# 21-LAN.net
KiCad netlist of a schematic drawn in Altium Designer
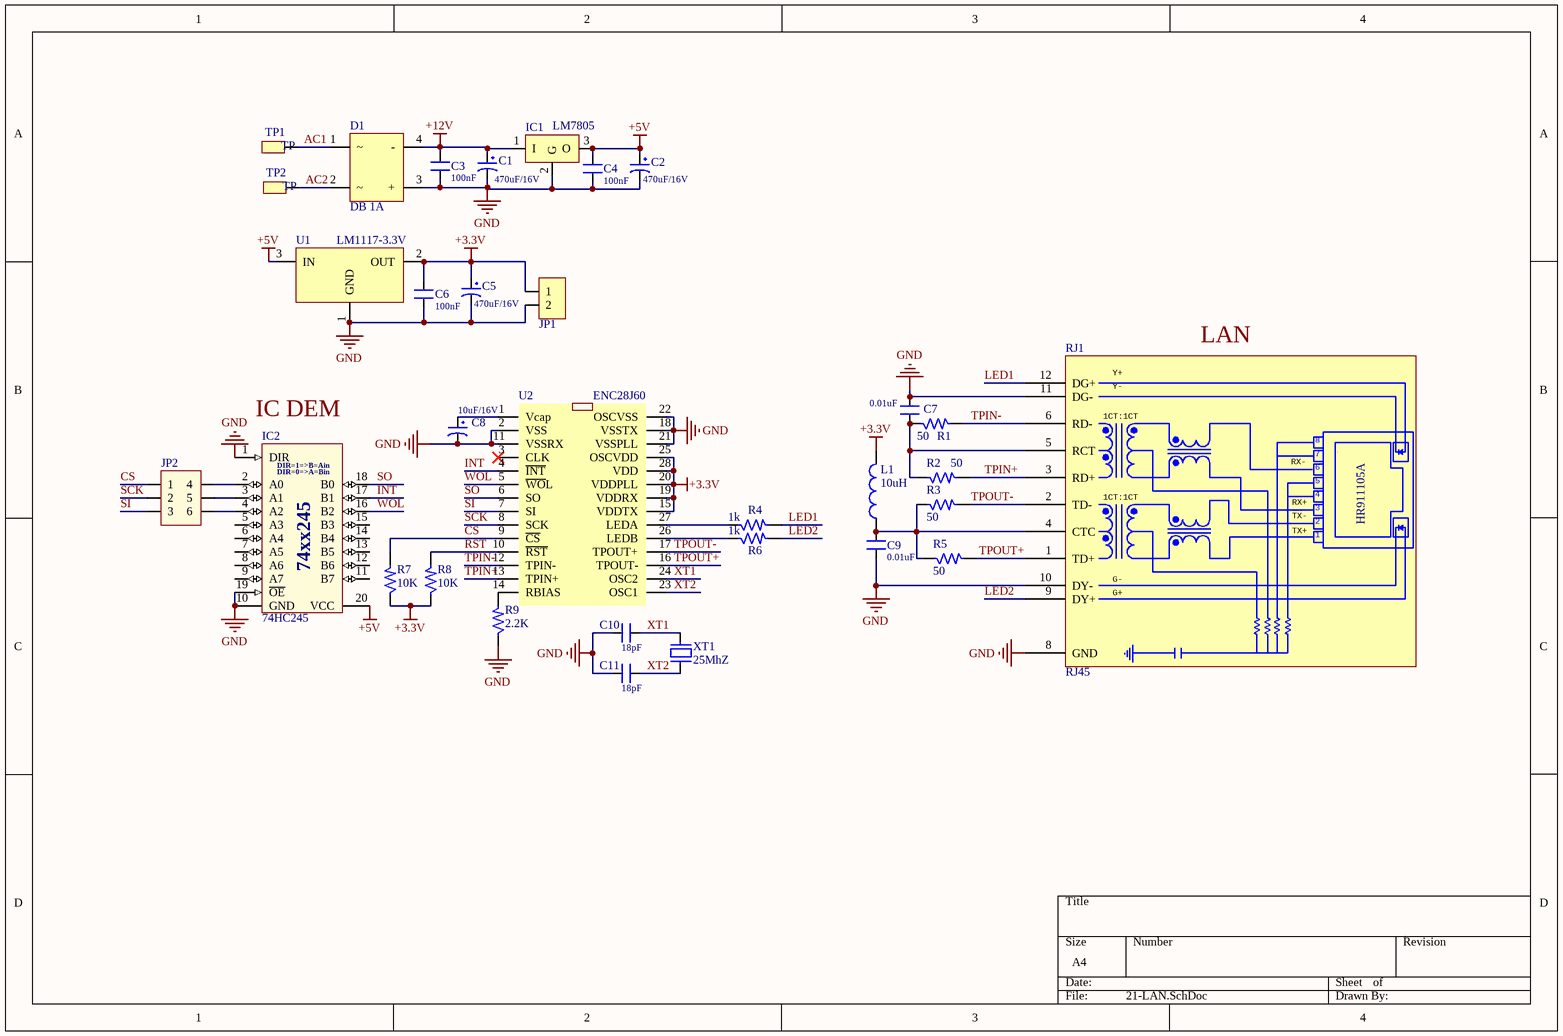
[diagram p0: 21-LAN.SchDoc]

(export (version "E")
  (design (tool "Eeschema 10.0.6"))
  (components
    (comp (ref "C1")
      (value "470uF/16V")
      (footprint "C-TANT-7343")
      (libsource (lib "MrQuan") (part "Capacitor"))
    )
    (comp (ref "C2")
      (value "470uF/16V")
      (footprint "C-TANT-7343")
      (libsource (lib "MrQuan") (part "Capacitor"))
    )
    (comp (ref "C3") (value "100nF") (footprint "CER-0805") (libsource (lib "MrQuan") (part "Ceramic")))
    (comp (ref "C4") (value "100nF") (footprint "CER-0805") (libsource (lib "MrQuan") (part "Ceramic")))
    (comp (ref "C5")
      (value "470uF/16V")
      (footprint "C-TANT-7343")
      (libsource (lib "MrQuan") (part "Capacitor"))
    )
    (comp (ref "C6") (value "100nF") (footprint "CER-0805") (libsource (lib "MrQuan") (part "Ceramic")))
    (comp (ref "C7") (value "0.01uF") (footprint "CER-0805") (libsource (lib "MrQuan") (part "Ceramic")))
    (comp (ref "C8")
      (value "10uF/16V")
      (footprint "C-TANT-7343")
      (libsource (lib "MrQuan") (part "Capacitor"))
    )
    (comp (ref "C9") (value "0.01uF") (footprint "CER-0805") (libsource (lib "MrQuan") (part "Ceramic")))
    (comp (ref "C10") (value "18pF") (footprint "CER-0805") (libsource (lib "MrQuan") (part "Ceramic")))
    (comp (ref "C11") (value "18pF") (footprint "CER-0805") (libsource (lib "MrQuan") (part "Ceramic")))
    (comp (ref "D1")
      (value "DB 1A")
      (footprint "D-DB-1A-SMD")
      (libsource (lib "doAnTotNghiep2017Lib") (part "DB"))
    )
    (comp (ref "IC1")
      (value "LM7805")
      (footprint "TO252-123")
      (description "Positive Voltage Regulator")
      (fields (field (name "PUBLISHER") "Altium Limited"))
      (libsource (lib "LIBRARY") (part "LM78xx"))
    )
    (comp (ref "IC2")
      (value "74HC245")
      (footprint "SO-20B")
      (description "Octal bus tranceiver; 3-state")
      (fields (field (name "COPYRIGHT BY") "VanDungEvn@gmail.com"))
      (libsource (lib "PART") (part "74245"))
    )
    (comp (ref "JP1")
      (value "JP2")
      (footprint "JP2-C1T")
      (description "WR-PHD 2.54 mm Angled Socket Header")
      (fields
        (field (name "MANUFACTURER") "Würth Elektronik eiSos GmbH")
        (field (name "PARTNO") "613002143121")
        (field (name "CREATED BY") "Karrer Zheng")
      )
      (libsource (lib "LIBRARY") (part "JP2"))
    )
    (comp (ref "JP2")
      (value "Connector 3x2")
      (footprint "JP3x2")
      (libsource (lib "syhaunguyen") (part "JP3x2"))
    )
    (comp (ref "L1")
      (value "10uH")
      (footprint "CER-0805")
      (description "Inductor")
      (fields (field (name "PUBLISHER") "Altium Limited"))
      (libsource (lib "VNSKILLS2014-ASM") (part "Inductor"))
    )
    (comp (ref "R1") (value "50") (footprint "RES-0805") (libsource (lib "MrQuan") (part "Res1/4W")))
    (comp (ref "R2") (value "50") (footprint "RES-0805") (libsource (lib "MrQuan") (part "Res1/4W")))
    (comp (ref "R3") (value "50") (footprint "RES-0805") (libsource (lib "MrQuan") (part "Res1/4W")))
    (comp (ref "R4") (value "1k") (footprint "RES-0805") (libsource (lib "MrQuan") (part "Res1/4W")))
    (comp (ref "R5") (value "50") (footprint "RES-0805") (libsource (lib "MrQuan") (part "Res1/4W")))
    (comp (ref "R6") (value "1k") (footprint "RES-0805") (libsource (lib "MrQuan") (part "Res1/4W")))
    (comp (ref "R7") (value "10K") (footprint "RES-0805") (libsource (lib "MrQuan") (part "Res1/4W")))
    (comp (ref "R8") (value "10K") (footprint "RES-0805") (libsource (lib "MrQuan") (part "Res1/4W")))
    (comp (ref "R9") (value "2.2K") (footprint "RES-0805") (libsource (lib "MrQuan") (part "Res1/4W")))
    (comp (ref "RJ1")
      (value "RJ45")
      (footprint "RJ45 Tranfomer")
      (libsource (lib "syhaunguyen") (part "RJ45 - Tranfomer"))
    )
    (comp (ref "TP1")
      (value "1")
      (footprint "TP")
      (description "CONNECT 1")
      (libsource (lib "PART") (part "TP"))
    )
    (comp (ref "TP2")
      (value "1")
      (footprint "TP")
      (description "CONNECT 1")
      (libsource (lib "PART") (part "TP"))
    )
    (comp (ref "U1")
      (value "LM1117-3.3V")
      (footprint "SOT223")
      (description "800mA Low-Dropout Linear Regulator")
      (fields (field (name "CREATOR") "Nguyen Ba Bien"))
      (libsource (lib "LIBRARY") (part "LM1117"))
    )
    (comp (ref "U2") (value "ENC28J60") (footprint "SOP 28N") (libsource (lib "MrQuan") (part "ENC28J60")))
    (comp (ref "XT1") (value "25MhZ") (footprint "XT SMD5032") (libsource (lib "MrQuan") (part "XT")))
  )
  (nets
    (net (code "1") (name "+3.3V") (class "Default")
      (node (ref "C5") (pin "1") (pinfunction "1_1") (pintype "passive"))
      (node (ref "C6") (pin "2") (pinfunction "2_2") (pintype "passive"))
      (node (ref "JP1") (pin "1") (pinfunction "1_1") (pintype "passive"))
      (node (ref "L1") (pin "2") (pinfunction "2_2") (pintype "passive"))
      (node (ref "R7") (pin "1") (pinfunction "1_1") (pintype "passive"))
      (node (ref "R8") (pin "1") (pinfunction "1_1") (pintype "passive"))
      (node (ref "U1") (pin "2") (pinfunction "OUT_2") (pintype "passive"))
      (node (ref "U2") (pin "15") (pinfunction "VDDTX_15") (pintype "passive"))
      (node (ref "U2") (pin "19") (pinfunction "VDDRX_19") (pintype "passive"))
      (node (ref "U2") (pin "20") (pinfunction "VDDPLL_20") (pintype "passive"))
      (node (ref "U2") (pin "25") (pinfunction "OSCVDD_25") (pintype "passive"))
      (node (ref "U2") (pin "28") (pinfunction "VDD_28") (pintype "passive"))
    )
    (net (code "2") (name "+5V") (class "Default")
      (node (ref "C2") (pin "1") (pinfunction "1_1") (pintype "passive"))
      (node (ref "C4") (pin "2") (pinfunction "2_2") (pintype "passive"))
      (node (ref "IC1") (pin "3") (pinfunction "O_3") (pintype "power_in"))
      (node (ref "IC2") (pin "20") (pinfunction "VCC_20") (pintype "power_in"))
      (node (ref "U1") (pin "3") (pinfunction "IN_3") (pintype "passive"))
    )
    (net (code "3") (name "+12V") (class "Default")
      (node (ref "C1") (pin "1") (pinfunction "1_1") (pintype "passive"))
      (node (ref "C3") (pin "2") (pinfunction "2_2") (pintype "passive"))
      (node (ref "D1") (pin "4") (pinfunction "-_4") (pintype "passive"))
      (node (ref "IC1") (pin "1") (pinfunction "I_1") (pintype "power_in"))
    )
    (net (code "4") (name "/AC1") (class "Default")
      (node (ref "D1") (pin "1") (pinfunction "~_1") (pintype "passive"))
      (node (ref "TP1") (pin "TP1") (pinfunction "0_TP1") (pintype "passive"))
    )
    (net (code "5") (name "/AC2") (class "Default")
      (node (ref "D1") (pin "2") (pinfunction "~_2") (pintype "passive"))
      (node (ref "TP2") (pin "TP1") (pinfunction "0_TP1") (pintype "passive"))
    )
    (net (code "6") (name "/CS") (class "Default")
      (node (ref "JP2") (pin "1") (pinfunction "1_1") (pintype "passive"))
      (node (ref "R7") (pin "2") (pinfunction "2_2") (pintype "passive"))
      (node (ref "U2") (pin "9") (pinfunction "~{CS}_9") (pintype "passive"))
    )
    (net (code "8") (name "/INT") (class "Default")
      (node (ref "IC2") (pin "17") (pinfunction "B1_17") (pintype "bidirectional"))
      (node (ref "U2") (pin "4") (pinfunction "~{INT}_4") (pintype "passive"))
    )
    (net (code "10") (name "/LED1") (class "Default")
      (node (ref "R4") (pin "2") (pinfunction "2_2") (pintype "passive"))
      (node (ref "RJ1") (pin "12") (pinfunction "DG+_12") (pintype "passive"))
    )
    (net (code "11") (name "/LED2") (class "Default")
      (node (ref "R6") (pin "2") (pinfunction "2_2") (pintype "passive"))
      (node (ref "RJ1") (pin "9") (pinfunction "DY+_9") (pintype "passive"))
    )
    (net (code "12") (name "/RST") (class "Default")
      (node (ref "R8") (pin "2") (pinfunction "2_2") (pintype "passive"))
      (node (ref "U2") (pin "10") (pinfunction "~{RST}_10") (pintype "passive"))
    )
    (net (code "13") (name "/SCK") (class "Default")
      (node (ref "JP2") (pin "2") (pinfunction "2_2") (pintype "passive"))
      (node (ref "U2") (pin "8") (pinfunction "SCK_8") (pintype "passive"))
    )
    (net (code "14") (name "/SI") (class "Default")
      (node (ref "JP2") (pin "3") (pinfunction "3_3") (pintype "passive"))
      (node (ref "U2") (pin "7") (pinfunction "SI_7") (pintype "passive"))
    )
    (net (code "15") (name "/SO") (class "Default")
      (node (ref "IC2") (pin "18") (pinfunction "B0_18") (pintype "bidirectional"))
      (node (ref "U2") (pin "6") (pinfunction "SO_6") (pintype "passive"))
    )
    (net (code "16") (name "/TPIN+") (class "Default")
      (node (ref "R2") (pin "2") (pinfunction "2_2") (pintype "passive"))
      (node (ref "RJ1") (pin "3") (pinfunction "RD+_3") (pintype "passive"))
      (node (ref "U2") (pin "13") (pinfunction "TPIN+_13") (pintype "passive"))
    )
    (net (code "17") (name "/TPIN-") (class "Default")
      (node (ref "R1") (pin "2") (pinfunction "2_2") (pintype "passive"))
      (node (ref "RJ1") (pin "6") (pinfunction "RD-_6") (pintype "passive"))
      (node (ref "U2") (pin "12") (pinfunction "TPIN-_12") (pintype "passive"))
    )
    (net (code "18") (name "/TPOUT+") (class "Default")
      (node (ref "R5") (pin "2") (pinfunction "2_2") (pintype "passive"))
      (node (ref "RJ1") (pin "1") (pinfunction "TD+_1") (pintype "passive"))
      (node (ref "U2") (pin "16") (pinfunction "TPOUT-_16") (pintype "passive"))
    )
    (net (code "19") (name "/TPOUT-") (class "Default")
      (node (ref "R3") (pin "2") (pinfunction "2_2") (pintype "passive"))
      (node (ref "RJ1") (pin "2") (pinfunction "TD-_2") (pintype "passive"))
      (node (ref "U2") (pin "17") (pinfunction "TPOUT+_17") (pintype "passive"))
    )
    (net (code "20") (name "/WOL") (class "Default")
      (node (ref "IC2") (pin "16") (pinfunction "B2_16") (pintype "bidirectional"))
      (node (ref "U2") (pin "5") (pinfunction "~{WO}L_5") (pintype "passive"))
    )
    (net (code "21") (name "/XT1") (class "Default")
      (node (ref "C10") (pin "1") (pinfunction "1_1") (pintype "passive"))
      (node (ref "U2") (pin "24") (pinfunction "OSC2_24") (pintype "passive"))
      (node (ref "XT1") (pin "2") (pinfunction "2_2") (pintype "passive"))
    )
    (net (code "22") (name "/XT2") (class "Default")
      (node (ref "C11") (pin "1") (pinfunction "1_1") (pintype "passive"))
      (node (ref "U2") (pin "23") (pinfunction "OSC1_23") (pintype "passive"))
      (node (ref "XT1") (pin "1") (pinfunction "1_1") (pintype "passive"))
    )
    (net (code "23") (name "GND") (class "Default")
      (node (ref "C1") (pin "2") (pinfunction "2_2") (pintype "passive"))
      (node (ref "C10") (pin "2") (pinfunction "2_2") (pintype "passive"))
      (node (ref "C11") (pin "2") (pinfunction "2_2") (pintype "passive"))
      (node (ref "C2") (pin "2") (pinfunction "2_2") (pintype "passive"))
      (node (ref "C3") (pin "1") (pinfunction "1_1") (pintype "passive"))
      (node (ref "C4") (pin "1") (pinfunction "1_1") (pintype "passive"))
      (node (ref "C5") (pin "2") (pinfunction "2_2") (pintype "passive"))
      (node (ref "C6") (pin "1") (pinfunction "1_1") (pintype "passive"))
      (node (ref "C7") (pin "2") (pinfunction "2_2") (pintype "passive"))
      (node (ref "C8") (pin "2") (pinfunction "2_2") (pintype "passive"))
      (node (ref "C9") (pin "2") (pinfunction "2_2") (pintype "passive"))
      (node (ref "D1") (pin "3") (pinfunction "+_3") (pintype "passive"))
      (node (ref "IC1") (pin "2") (pinfunction "G_2") (pintype "power_in"))
      (node (ref "IC2") (pin "1") (pinfunction "DIR_1") (pintype "input"))
      (node (ref "IC2") (pin "10") (pinfunction "GND_10") (pintype "power_in"))
      (node (ref "IC2") (pin "19") (pinfunction "~{OE}_19") (pintype "input"))
      (node (ref "JP1") (pin "2") (pinfunction "2_2") (pintype "passive"))
      (node (ref "R9") (pin "1") (pinfunction "1_1") (pintype "passive"))
      (node (ref "RJ1") (pin "10") (pinfunction "DY-_10") (pintype "passive"))
      (node (ref "RJ1") (pin "11") (pinfunction "DG-_11") (pintype "passive"))
      (node (ref "RJ1") (pin "8") (pinfunction "GND_8") (pintype "power_in"))
      (node (ref "U1") (pin "1") (pinfunction "GND_1") (pintype "passive"))
      (node (ref "U2") (pin "11") (pinfunction "VSSRX_11") (pintype "passive"))
      (node (ref "U2") (pin "18") (pinfunction "VSSTX_18") (pintype "passive"))
      (node (ref "U2") (pin "2") (pinfunction "VSS_2") (pintype "passive"))
      (node (ref "U2") (pin "21") (pinfunction "VSSPLL_21") (pintype "passive"))
      (node (ref "U2") (pin "22") (pinfunction "OSCVSS_22") (pintype "passive"))
    )
    (net (code "24") (name "Net-(IC2-A0)") (class "Default")
      (node (ref "IC2") (pin "2") (pinfunction "A0_2") (pintype "bidirectional"))
      (node (ref "JP2") (pin "4") (pinfunction "4_4") (pintype "passive"))
    )
    (net (code "25") (name "Net-(IC2-A1)") (class "Default")
      (node (ref "IC2") (pin "3") (pinfunction "A1_3") (pintype "bidirectional"))
      (node (ref "JP2") (pin "5") (pinfunction "5_5") (pintype "passive"))
    )
    (net (code "26") (name "Net-(IC2-A2)") (class "Default")
      (node (ref "IC2") (pin "4") (pinfunction "A2_4") (pintype "bidirectional"))
      (node (ref "JP2") (pin "6") (pinfunction "6_6") (pintype "passive"))
    )
    (net (code "27") (name "Net-(RJ1-CTC)") (class "Default")
      (node (ref "C9") (pin "1") (pinfunction "1_1") (pintype "passive"))
      (node (ref "L1") (pin "1") (pinfunction "1_1") (pintype "passive"))
      (node (ref "R3") (pin "1") (pinfunction "1_1") (pintype "passive"))
      (node (ref "R5") (pin "1") (pinfunction "1_1") (pintype "passive"))
      (node (ref "RJ1") (pin "4") (pinfunction "CTC_4") (pintype "passive"))
    )
    (net (code "28") (name "Net-(RJ1-RCT)") (class "Default")
      (node (ref "C7") (pin "1") (pinfunction "1_1") (pintype "passive"))
      (node (ref "R1") (pin "1") (pinfunction "1_1") (pintype "passive"))
      (node (ref "R2") (pin "1") (pinfunction "1_1") (pintype "passive"))
      (node (ref "RJ1") (pin "5") (pinfunction "RCT_5") (pintype "passive"))
    )
    (net (code "29") (name "Net-(U2-LEDA)") (class "Default")
      (node (ref "R4") (pin "1") (pinfunction "1_1") (pintype "passive"))
      (node (ref "U2") (pin "27") (pinfunction "LEDA_27") (pintype "passive"))
    )
    (net (code "30") (name "Net-(U2-LEDB)") (class "Default")
      (node (ref "R6") (pin "1") (pinfunction "1_1") (pintype "passive"))
      (node (ref "U2") (pin "26") (pinfunction "LEDB_26") (pintype "passive"))
    )
    (net (code "31") (name "Net-(U2-RBIAS)") (class "Default")
      (node (ref "R9") (pin "2") (pinfunction "2_2") (pintype "passive"))
      (node (ref "U2") (pin "14") (pinfunction "RBIAS_14") (pintype "passive"))
    )
    (net (code "32") (name "Net-(U2-Vcap)") (class "Default")
      (node (ref "C8") (pin "1") (pinfunction "1_1") (pintype "passive"))
      (node (ref "U2") (pin "1") (pinfunction "Vcap_1") (pintype "passive"))
    )
    (net (code "33") (name "unconnected-(IC2-A3-Pad5)") (class "Default")
      (node (ref "IC2") (pin "5") (pinfunction "A3_5") (pintype "bidirectional"))
    )
    (net (code "34") (name "unconnected-(IC2-A4-Pad6)") (class "Default")
      (node (ref "IC2") (pin "6") (pinfunction "A4_6") (pintype "bidirectional"))
    )
    (net (code "35") (name "unconnected-(IC2-A5-Pad7)") (class "Default")
      (node (ref "IC2") (pin "7") (pinfunction "A5_7") (pintype "bidirectional"))
    )
    (net (code "36") (name "unconnected-(IC2-A6-Pad8)") (class "Default")
      (node (ref "IC2") (pin "8") (pinfunction "A6_8") (pintype "bidirectional"))
    )
    (net (code "37") (name "unconnected-(IC2-A7-Pad9)") (class "Default")
      (node (ref "IC2") (pin "9") (pinfunction "A7_9") (pintype "bidirectional"))
    )
    (net (code "38") (name "unconnected-(IC2-B3-Pad15)") (class "Default")
      (node (ref "IC2") (pin "15") (pinfunction "B3_15") (pintype "bidirectional"))
    )
    (net (code "39") (name "unconnected-(IC2-B4-Pad14)") (class "Default")
      (node (ref "IC2") (pin "14") (pinfunction "B4_14") (pintype "bidirectional"))
    )
    (net (code "40") (name "unconnected-(IC2-B5-Pad13)") (class "Default")
      (node (ref "IC2") (pin "13") (pinfunction "B5_13") (pintype "bidirectional"))
    )
    (net (code "41") (name "unconnected-(IC2-B6-Pad12)") (class "Default")
      (node (ref "IC2") (pin "12") (pinfunction "B6_12") (pintype "bidirectional"))
    )
    (net (code "42") (name "unconnected-(IC2-B7-Pad11)") (class "Default")
      (node (ref "IC2") (pin "11") (pinfunction "B7_11") (pintype "bidirectional"))
    )
    (net (code "43") (name "unconnected-(U2-CLK-Pad3)") (class "Default")
      (node (ref "U2") (pin "3") (pinfunction "CLK_3") (pintype "passive+no_connect"))
    )
  )
)
